# TLE5010.net
KiCad netlist of a schematic drawn in EAGLE
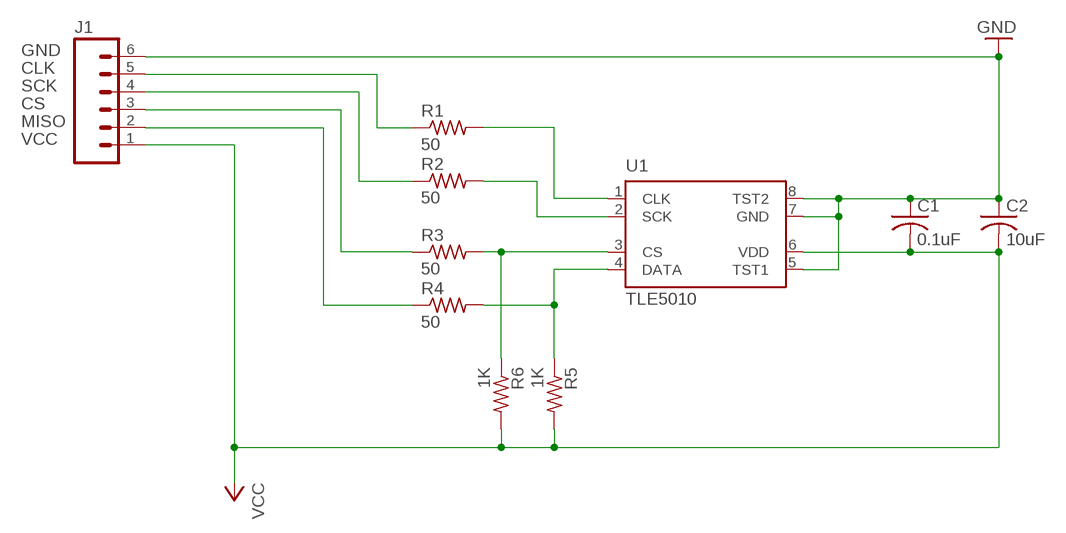
[diagram p0: schematic, sheet 1]

(export (version "E")
  (design (tool "Eeschema 10.0.6"))
  (components
    (comp (ref "C1")
      (value "0.1uF")
      (footprint "eagle-import:C1206")
      (libsource (lib "eagle-import") (part "C-USC1206"))
    )
    (comp (ref "C2")
      (value "10uF")
      (footprint "eagle-import:C1206")
      (libsource (lib "eagle-import") (part "C-USC1206"))
    )
    (comp (ref "J1")
      (value "M06POLAR_LOCK")
      (footprint "eagle-import:MOLEX-1X6_LOCK")
      (libsource (lib "eagle-import") (part "M06POLAR_LOCK"))
    )
    (comp (ref "R1")
      (value "50")
      (footprint "eagle-import:R1206")
      (libsource (lib "eagle-import") (part "R-US_R1206"))
    )
    (comp (ref "R2")
      (value "50")
      (footprint "eagle-import:R1206")
      (libsource (lib "eagle-import") (part "R-US_R1206"))
    )
    (comp (ref "R3")
      (value "50")
      (footprint "eagle-import:R1206")
      (libsource (lib "eagle-import") (part "R-US_R1206"))
    )
    (comp (ref "R4")
      (value "50")
      (footprint "eagle-import:R1206")
      (libsource (lib "eagle-import") (part "R-US_R1206"))
    )
    (comp (ref "R5")
      (value "1K")
      (footprint "eagle-import:R1206")
      (libsource (lib "eagle-import") (part "R-US_R1206"))
    )
    (comp (ref "R6")
      (value "1K")
      (footprint "eagle-import:R1206")
      (libsource (lib "eagle-import") (part "R-US_R1206"))
    )
    (comp (ref "U1")
      (value "TLE5010")
      (footprint "eagle-import:PG-DSO-8")
      (libsource (lib "eagle-import") (part "TLE5010"))
    )
  )
  (nets
    (net (code "1") (name "/CLK") (class "Default")
      (node (ref "J1") (pin "5") (pinfunction "5_5") (pintype "passive"))
      (node (ref "R1") (pin "1") (pinfunction "1_1") (pintype "passive"))
    )
    (net (code "2") (name "/CS") (class "Default")
      (node (ref "J1") (pin "3") (pinfunction "3_3") (pintype "passive"))
      (node (ref "R3") (pin "1") (pinfunction "1_1") (pintype "passive"))
    )
    (net (code "3") (name "/MISO") (class "Default")
      (node (ref "J1") (pin "2") (pinfunction "2_2") (pintype "passive"))
      (node (ref "R4") (pin "1") (pinfunction "1_1") (pintype "passive"))
    )
    (net (code "4") (name "/SCK") (class "Default")
      (node (ref "J1") (pin "4") (pinfunction "4_4") (pintype "passive"))
      (node (ref "R2") (pin "1") (pinfunction "1_1") (pintype "passive"))
    )
    (net (code "5") (name "GND") (class "Default")
      (node (ref "C1") (pin "1") (pinfunction "1_1") (pintype "passive"))
      (node (ref "C2") (pin "1") (pinfunction "1_1") (pintype "passive"))
      (node (ref "J1") (pin "6") (pinfunction "6_6") (pintype "passive"))
      (node (ref "U1") (pin "5") (pinfunction "TST1_5") (pintype "bidirectional"))
      (node (ref "U1") (pin "7") (pinfunction "GND_7") (pintype "power_in"))
      (node (ref "U1") (pin "8") (pinfunction "TST2_8") (pintype "bidirectional"))
    )
    (net (code "6") (name "Net-(U1-CLK)") (class "Default")
      (node (ref "R1") (pin "2") (pinfunction "2_2") (pintype "passive"))
      (node (ref "U1") (pin "1") (pinfunction "CLK_1") (pintype "input"))
    )
    (net (code "7") (name "Net-(U1-CS)") (class "Default")
      (node (ref "R3") (pin "2") (pinfunction "2_2") (pintype "passive"))
      (node (ref "R6") (pin "1") (pinfunction "1_1") (pintype "passive"))
      (node (ref "U1") (pin "3") (pinfunction "CS_3") (pintype "input"))
    )
    (net (code "8") (name "Net-(U1-DATA)") (class "Default")
      (node (ref "R4") (pin "2") (pinfunction "2_2") (pintype "passive"))
      (node (ref "R5") (pin "1") (pinfunction "1_1") (pintype "passive"))
      (node (ref "U1") (pin "4") (pinfunction "DATA_4") (pintype "bidirectional"))
    )
    (net (code "9") (name "Net-(U1-SCK)") (class "Default")
      (node (ref "R2") (pin "2") (pinfunction "2_2") (pintype "passive"))
      (node (ref "U1") (pin "2") (pinfunction "SCK_2") (pintype "input"))
    )
    (net (code "10") (name "VCC") (class "Default")
      (node (ref "C1") (pin "2") (pinfunction "2_2") (pintype "passive"))
      (node (ref "C2") (pin "2") (pinfunction "2_2") (pintype "passive"))
      (node (ref "J1") (pin "1") (pinfunction "1_1") (pintype "passive"))
      (node (ref "R5") (pin "2") (pinfunction "2_2") (pintype "passive"))
      (node (ref "R6") (pin "2") (pinfunction "2_2") (pintype "passive"))
      (node (ref "U1") (pin "6") (pinfunction "VDD_6") (pintype "power_in"))
    )
  )
)
